# RSxx.net
KiCad netlist of a schematic drawn in Altium Designer
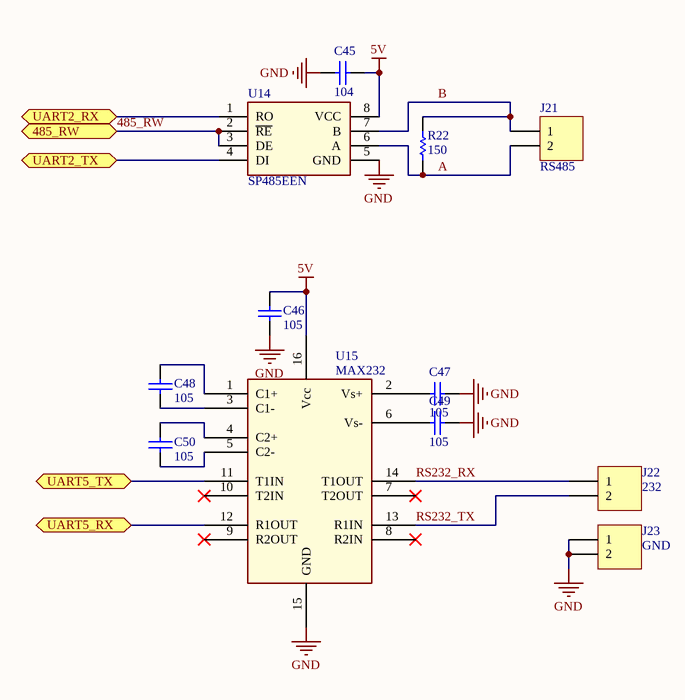
[diagram p0: RSxx.SchDoc]

(export (version "E")
  (design (tool "Eeschema 10.0.6"))
  (components
    (comp (ref "C45")
      (value "104")
      (footprint "C0603")
      (description "CAP CER 0.1UF 16V Y5V 0402")
      (fields
        (field (name "MANUFACTURER") "Yageo")
        (field (name "DIGI-KEY PART NUMBER") "311-1047-1-ND")
        (field (name "PUBLISHER") "Altium Limited")
      )
      (libsource (lib "RobotClub") (part "Cap_SMT"))
    )
    (comp (ref "C46")
      (value "105")
      (footprint "C0603")
      (description "CAP CER 0.1UF 16V Y5V 0402")
      (fields
        (field (name "MANUFACTURER") "Yageo")
        (field (name "DIGI-KEY PART NUMBER") "311-1047-1-ND")
        (field (name "PUBLISHER") "Altium Limited")
      )
      (libsource (lib "RobotClub") (part "Cap_SMT"))
    )
    (comp (ref "C47")
      (value "105")
      (footprint "C0603")
      (description "CAP CER 0.1UF 16V Y5V 0402")
      (fields
        (field (name "MANUFACTURER") "Yageo")
        (field (name "DIGI-KEY PART NUMBER") "311-1047-1-ND")
        (field (name "PUBLISHER") "Altium Limited")
      )
      (libsource (lib "RobotClub") (part "Cap_SMT"))
    )
    (comp (ref "C48")
      (value "105")
      (footprint "C0603")
      (description "CAP CER 0.1UF 16V Y5V 0402")
      (fields
        (field (name "MANUFACTURER") "Yageo")
        (field (name "DIGI-KEY PART NUMBER") "311-1047-1-ND")
        (field (name "PUBLISHER") "Altium Limited")
      )
      (libsource (lib "RobotClub") (part "Cap_SMT"))
    )
    (comp (ref "C49")
      (value "105")
      (footprint "C0603")
      (description "CAP CER 0.1UF 16V Y5V 0402")
      (fields
        (field (name "MANUFACTURER") "Yageo")
        (field (name "DIGI-KEY PART NUMBER") "311-1047-1-ND")
        (field (name "PUBLISHER") "Altium Limited")
      )
      (libsource (lib "RobotClub") (part "Cap_SMT"))
    )
    (comp (ref "C50")
      (value "105")
      (footprint "C0603")
      (description "CAP CER 0.1UF 16V Y5V 0402")
      (fields
        (field (name "MANUFACTURER") "Yageo")
        (field (name "DIGI-KEY PART NUMBER") "311-1047-1-ND")
        (field (name "PUBLISHER") "Altium Limited")
      )
      (libsource (lib "RobotClub") (part "Cap_SMT"))
    )
    (comp (ref "J21")
      (value "RS485")
      (footprint "DOMINO NORMAL 2")
      (description "Header, 2-Pin")
      (fields (field (name "PUBLISHER") "Altium Limited"))
      (libsource (lib "RobotClub") (part "Header 2"))
    )
    (comp (ref "J22")
      (value "232")
      (footprint "DOMINO NORMAL 2")
      (description "Header, 2-Pin")
      (fields (field (name "PUBLISHER") "Altium Limited"))
      (libsource (lib "RobotClub") (part "Header 2"))
    )
    (comp (ref "J23")
      (value "GND")
      (footprint "DOMINO NORMAL 2")
      (description "Header, 2-Pin")
      (fields (field (name "PUBLISHER") "Altium Limited"))
      (libsource (lib "RobotClub") (part "Header 2"))
    )
    (comp (ref "R22")
      (value "150")
      (footprint "R0603")
      (description "Resistor SMD 5%")
      (fields
        (field (name "DIGI-KEY PART NUMBER") "P3.24KLTR-ND")
        (field (name "MANUFACTURER") "Panasonic Electronic Components")
        (field (name "PUBLISHER") "Altium Limited")
      )
      (libsource (lib "RobotClub") (part "R_SMD5"))
    )
    (comp (ref "U14") (value "SP485EEN") (footprint "SO8_L") (libsource (lib "RobotClub") (part "SP485EEN")))
    (comp (ref "U15") (value "MAX232") (footprint "SOIC16_M") (libsource (lib "RobotClub") (part "MAX232")))
  )
  (nets
    (net (code "1") (name "/485_RW") (class "Default")
      (node (ref "U14") (pin "2") (pinfunction "~{RE}_2") (pintype "passive"))
      (node (ref "U14") (pin "3") (pinfunction "DE_3") (pintype "passive"))
    )
    (net (code "2") (name "/A") (class "Default")
      (node (ref "J21") (pin "2") (pinfunction "2_2") (pintype "passive"))
      (node (ref "R22") (pin "1") (pinfunction "1_1") (pintype "passive"))
      (node (ref "U14") (pin "6") (pinfunction "A_6") (pintype "passive"))
    )
    (net (code "3") (name "/B") (class "Default")
      (node (ref "J21") (pin "1") (pinfunction "1_1") (pintype "passive"))
      (node (ref "R22") (pin "2") (pinfunction "2_2") (pintype "passive"))
      (node (ref "U14") (pin "7") (pinfunction "B_7") (pintype "passive"))
    )
    (net (code "4") (name "/RS232_RX") (class "Default")
      (node (ref "J22") (pin "1") (pinfunction "1_1") (pintype "passive"))
      (node (ref "U15") (pin "14") (pinfunction "T1OUT_14") (pintype "passive"))
    )
    (net (code "5") (name "/RS232_TX") (class "Default")
      (node (ref "J22") (pin "2") (pinfunction "2_2") (pintype "passive"))
      (node (ref "U15") (pin "13") (pinfunction "R1IN_13") (pintype "passive"))
    )
    (net (code "6") (name "/UART2_RX") (class "Default")
      (node (ref "U14") (pin "1") (pinfunction "RO_1") (pintype "passive"))
    )
    (net (code "7") (name "/UART2_TX") (class "Default")
      (node (ref "U14") (pin "4") (pinfunction "DI_4") (pintype "passive"))
    )
    (net (code "8") (name "/UART5_RX") (class "Default")
      (node (ref "U15") (pin "12") (pinfunction "R1OUT_12") (pintype "passive"))
    )
    (net (code "9") (name "/UART5_TX") (class "Default")
      (node (ref "U15") (pin "11") (pinfunction "T1IN_11") (pintype "passive"))
    )
    (net (code "10") (name "5V") (class "Default")
      (node (ref "C45") (pin "2") (pinfunction "2_2") (pintype "passive"))
      (node (ref "C46") (pin "2") (pinfunction "2_2") (pintype "passive"))
      (node (ref "U14") (pin "8") (pinfunction "VCC_8") (pintype "passive"))
      (node (ref "U15") (pin "16") (pinfunction "Vcc_16") (pintype "passive"))
    )
    (net (code "11") (name "GND") (class "Default")
      (node (ref "C45") (pin "1") (pinfunction "1_1") (pintype "passive"))
      (node (ref "C46") (pin "1") (pinfunction "1_1") (pintype "passive"))
      (node (ref "C47") (pin "2") (pinfunction "2_2") (pintype "passive"))
      (node (ref "C49") (pin "2") (pinfunction "2_2") (pintype "passive"))
      (node (ref "J23") (pin "1") (pinfunction "1_1") (pintype "passive"))
      (node (ref "J23") (pin "2") (pinfunction "2_2") (pintype "passive"))
      (node (ref "U14") (pin "5") (pinfunction "GND_5") (pintype "passive"))
      (node (ref "U15") (pin "15") (pinfunction "GND_15") (pintype "passive"))
    )
    (net (code "12") (name "Net-(U15-C1+)") (class "Default")
      (node (ref "C48") (pin "2") (pinfunction "2_2") (pintype "passive"))
      (node (ref "U15") (pin "1") (pinfunction "C1+_1") (pintype "passive"))
    )
    (net (code "13") (name "Net-(U15-C1-)") (class "Default")
      (node (ref "C48") (pin "1") (pinfunction "1_1") (pintype "passive"))
      (node (ref "U15") (pin "3") (pinfunction "C1-_3") (pintype "passive"))
    )
    (net (code "14") (name "Net-(U15-C2+)") (class "Default")
      (node (ref "C50") (pin "2") (pinfunction "2_2") (pintype "passive"))
      (node (ref "U15") (pin "4") (pinfunction "C2+_4") (pintype "passive"))
    )
    (net (code "15") (name "Net-(U15-C2-)") (class "Default")
      (node (ref "C50") (pin "1") (pinfunction "1_1") (pintype "passive"))
      (node (ref "U15") (pin "5") (pinfunction "C2-_5") (pintype "passive"))
    )
    (net (code "16") (name "Net-(U15-Vs+)") (class "Default")
      (node (ref "C47") (pin "1") (pinfunction "1_1") (pintype "passive"))
      (node (ref "U15") (pin "2") (pinfunction "Vs+_2") (pintype "passive"))
    )
    (net (code "17") (name "Net-(U15-Vs-)") (class "Default")
      (node (ref "C49") (pin "1") (pinfunction "1_1") (pintype "passive"))
      (node (ref "U15") (pin "6") (pinfunction "Vs-_6") (pintype "passive"))
    )
    (net (code "18") (name "unconnected-(U15-R2IN-Pad8)") (class "Default")
      (node (ref "U15") (pin "8") (pinfunction "R2IN_8") (pintype "passive+no_connect"))
    )
    (net (code "19") (name "unconnected-(U15-R2OUT-Pad9)") (class "Default")
      (node (ref "U15") (pin "9") (pinfunction "R2OUT_9") (pintype "passive+no_connect"))
    )
    (net (code "20") (name "unconnected-(U15-T2IN-Pad10)") (class "Default")
      (node (ref "U15") (pin "10") (pinfunction "T2IN_10") (pintype "passive+no_connect"))
    )
    (net (code "21") (name "unconnected-(U15-T2OUT-Pad7)") (class "Default")
      (node (ref "U15") (pin "7") (pinfunction "T2OUT_7") (pintype "passive+no_connect"))
    )
  )
)
